# Main.net
KiCad netlist of a schematic drawn in Altium Designer
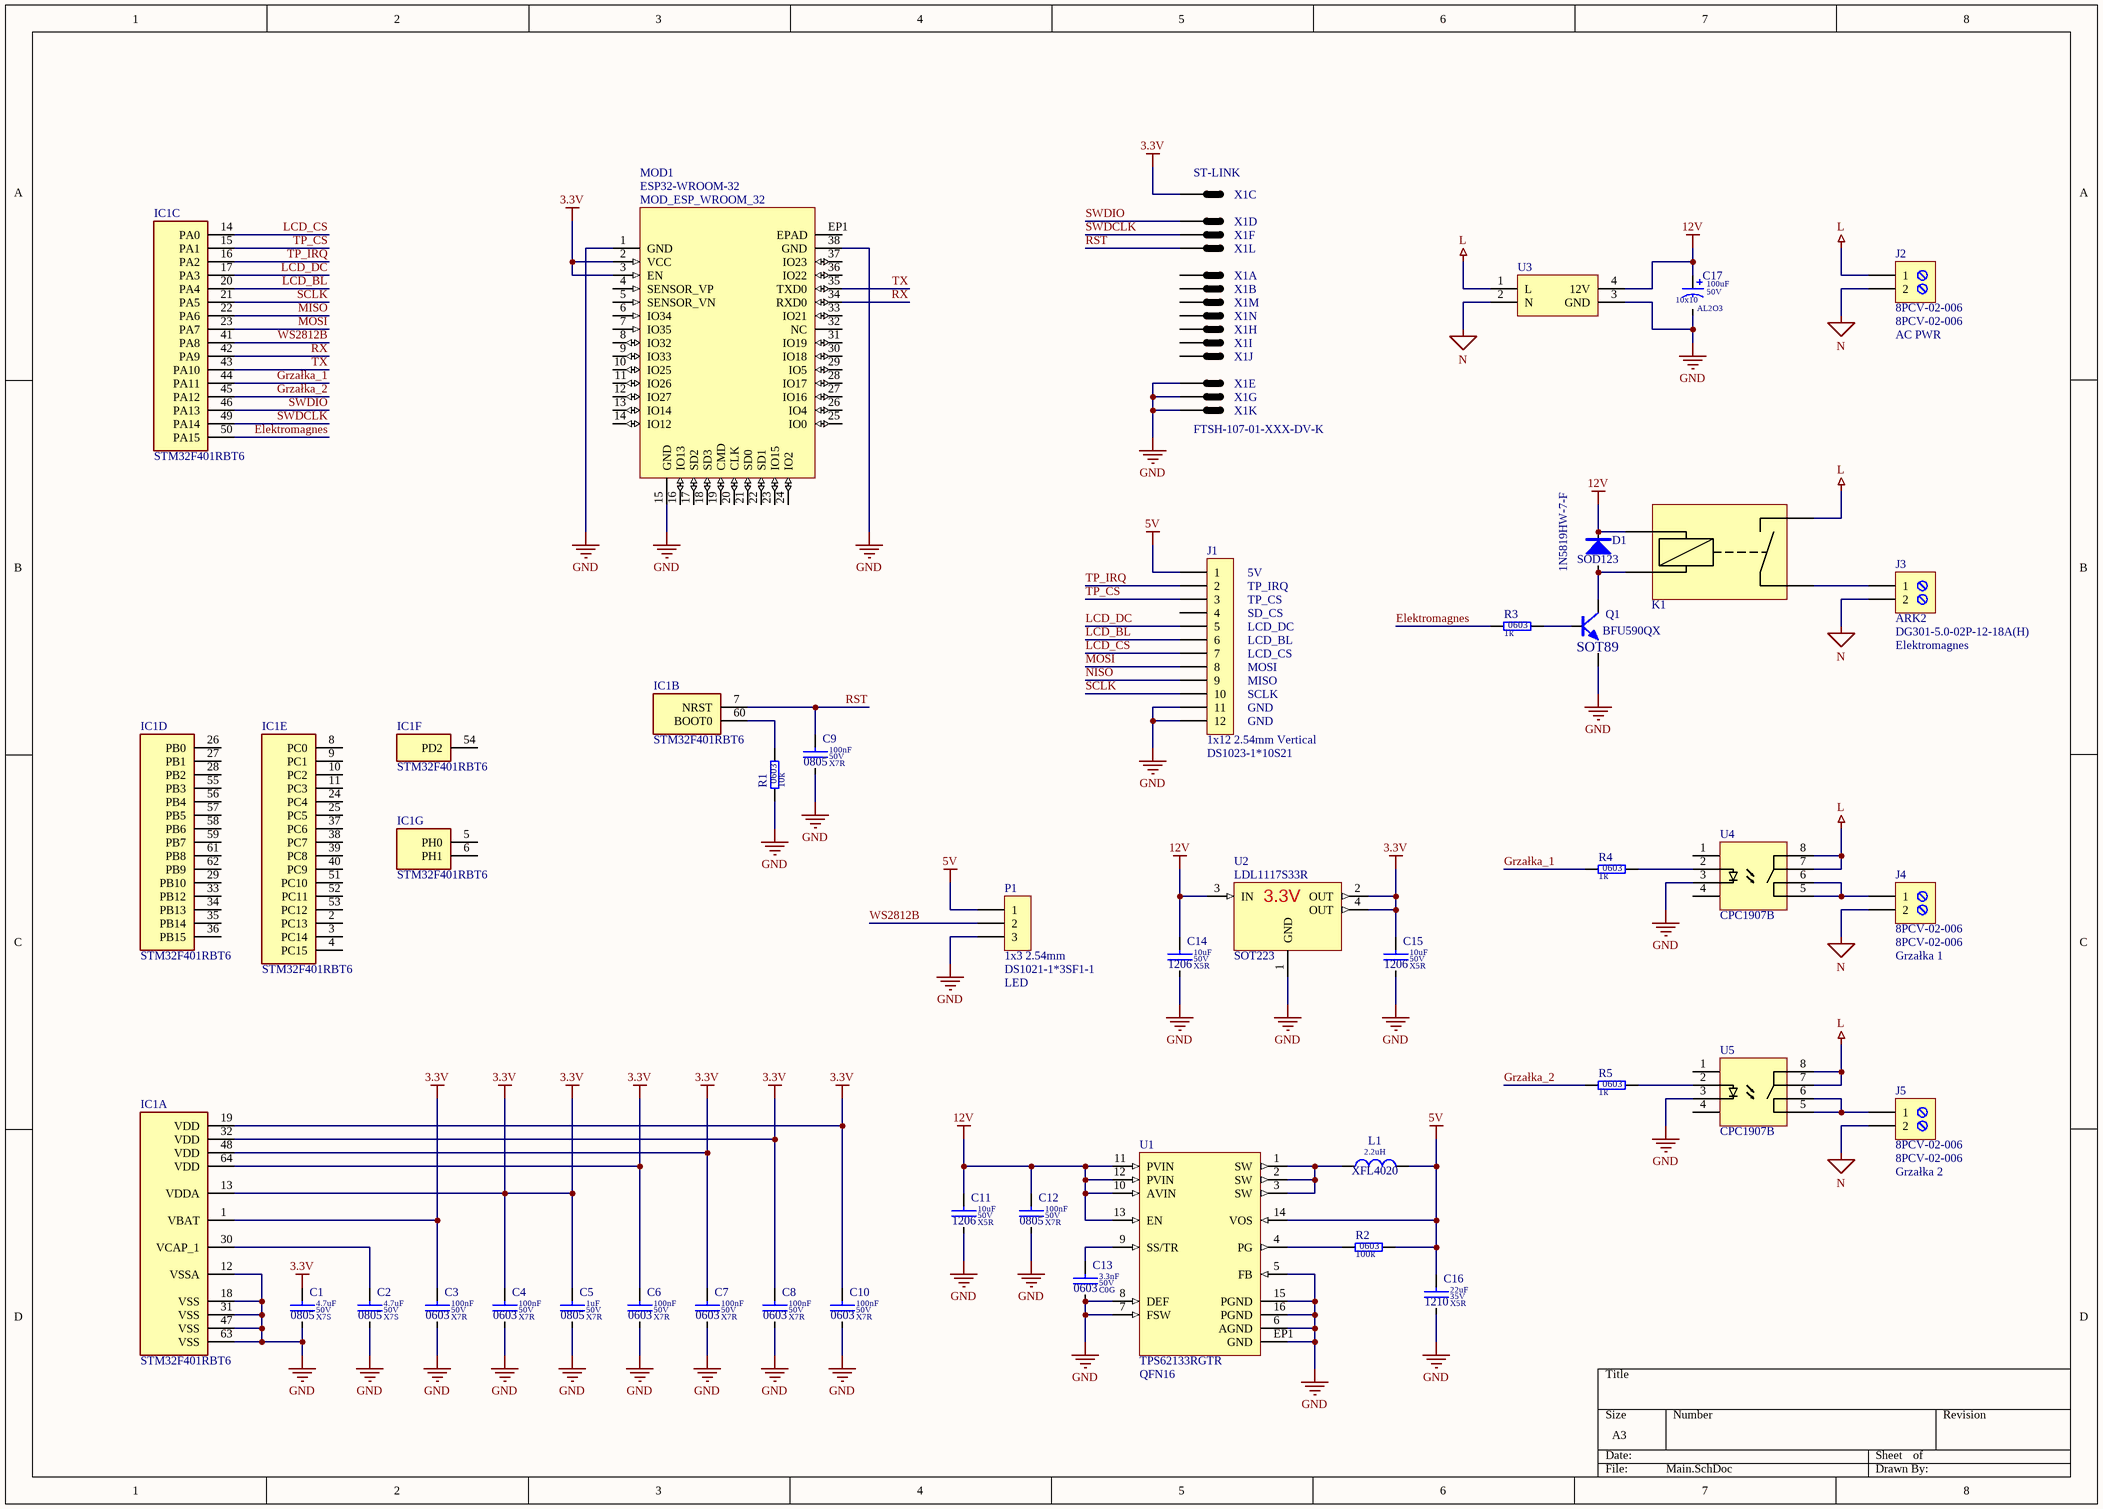
[diagram p0: Main.SchDoc]

(export (version "E")
  (design (tool "Eeschema 10.0.6"))
  (components
    (comp (ref "C1")
      (value "4.7uF")
      (footprint "C_0805_2012")
      (description "Capacitor")
      (fields
        (field (name "DIELECTRIC") "X7S")
        (field (name "VOLTAGE") "50V")
        (field (name "SCH_FOOTPRINT") "0805")
        (field (name "PART NUMBER") "C_4.7uF_50V_X7S_0805_10")
        (field (name "MANUFACTURER") "Murata")
      )
      (libsource (lib "Library") (part "C"))
    )
    (comp (ref "C2")
      (value "4.7uF")
      (footprint "C_0805_2012")
      (description "Capacitor")
      (fields
        (field (name "DIELECTRIC") "X7S")
        (field (name "VOLTAGE") "50V")
        (field (name "SCH_FOOTPRINT") "0805")
        (field (name "PART NUMBER") "C_4.7uF_50V_X7S_0805_10")
        (field (name "MANUFACTURER") "Murata")
      )
      (libsource (lib "Library") (part "C"))
    )
    (comp (ref "C3")
      (value "100nF")
      (footprint "C_0603_1608")
      (description "Capacitor")
      (fields
        (field (name "DIELECTRIC") "X7R")
        (field (name "VOLTAGE") "50V")
        (field (name "SCH_FOOTPRINT") "0603")
        (field (name "PART NUMBER") "C_100nF_50V_X7R_0603_5")
        (field (name "MANUFACTURER") "Samsung")
      )
      (libsource (lib "Library") (part "C"))
    )
    (comp (ref "C4")
      (value "100nF")
      (footprint "C_0603_1608")
      (description "Capacitor")
      (fields
        (field (name "DIELECTRIC") "X7R")
        (field (name "VOLTAGE") "50V")
        (field (name "SCH_FOOTPRINT") "0603")
        (field (name "PART NUMBER") "C_100nF_50V_X7R_0603_5")
        (field (name "MANUFACTURER") "Samsung")
      )
      (libsource (lib "Library") (part "C"))
    )
    (comp (ref "C5")
      (value "1uF")
      (footprint "C_0805_2012")
      (description "Capacitor")
      (fields
        (field (name "DIELECTRIC") "X7R")
        (field (name "VOLTAGE") "50V")
        (field (name "SCH_FOOTPRINT") "0805")
        (field (name "PART NUMBER") "C_1uF_50V_X7R_0805_10")
        (field (name "MANUFACTURER") "AVX")
      )
      (libsource (lib "Library") (part "C"))
    )
    (comp (ref "C6")
      (value "100nF")
      (footprint "C_0603_1608")
      (description "Capacitor")
      (fields
        (field (name "DIELECTRIC") "X7R")
        (field (name "VOLTAGE") "50V")
        (field (name "SCH_FOOTPRINT") "0603")
        (field (name "PART NUMBER") "C_100nF_50V_X7R_0603_5")
        (field (name "MANUFACTURER") "Samsung")
      )
      (libsource (lib "Library") (part "C"))
    )
    (comp (ref "C7")
      (value "100nF")
      (footprint "C_0603_1608")
      (description "Capacitor")
      (fields
        (field (name "DIELECTRIC") "X7R")
        (field (name "VOLTAGE") "50V")
        (field (name "SCH_FOOTPRINT") "0603")
        (field (name "PART NUMBER") "C_100nF_50V_X7R_0603_5")
        (field (name "MANUFACTURER") "Samsung")
      )
      (libsource (lib "Library") (part "C"))
    )
    (comp (ref "C8")
      (value "100nF")
      (footprint "C_0603_1608")
      (description "Capacitor")
      (fields
        (field (name "DIELECTRIC") "X7R")
        (field (name "VOLTAGE") "50V")
        (field (name "SCH_FOOTPRINT") "0603")
        (field (name "PART NUMBER") "C_100nF_50V_X7R_0603_5")
        (field (name "MANUFACTURER") "Samsung")
      )
      (libsource (lib "Library") (part "C"))
    )
    (comp (ref "C9")
      (value "100nF")
      (footprint "C_0805_2012")
      (description "Capacitor")
      (fields
        (field (name "DIELECTRIC") "X7R")
        (field (name "VOLTAGE") "50V")
        (field (name "SCH_FOOTPRINT") "0805")
        (field (name "PART NUMBER") "C_100nF_50V_X7R_0805_10")
        (field (name "MANUFACTURER") "AVX")
      )
      (libsource (lib "Library") (part "C"))
    )
    (comp (ref "C10")
      (value "100nF")
      (footprint "C_0603_1608")
      (description "Capacitor")
      (fields
        (field (name "DIELECTRIC") "X7R")
        (field (name "VOLTAGE") "50V")
        (field (name "SCH_FOOTPRINT") "0603")
        (field (name "PART NUMBER") "C_100nF_50V_X7R_0603_5")
        (field (name "MANUFACTURER") "Samsung")
      )
      (libsource (lib "Library") (part "C"))
    )
    (comp (ref "C11")
      (value "10uF")
      (footprint "C_1206_3216")
      (description "Capacitor")
      (fields
        (field (name "DIELECTRIC") "X5R")
        (field (name "VOLTAGE") "50V")
        (field (name "SCH_FOOTPRINT") "1206")
        (field (name "PART NUMBER") "C_10uF_50V_X5R_1206_10")
        (field (name "MANUFACTURER") "Murata")
      )
      (libsource (lib "Library") (part "C"))
    )
    (comp (ref "C12")
      (value "100nF")
      (footprint "C_0805_2012")
      (description "Capacitor")
      (fields
        (field (name "DIELECTRIC") "X7R")
        (field (name "VOLTAGE") "50V")
        (field (name "SCH_FOOTPRINT") "0805")
        (field (name "PART NUMBER") "C_100nF_50V_X7R_0805_10")
        (field (name "MANUFACTURER") "AVX")
      )
      (libsource (lib "Library") (part "C"))
    )
    (comp (ref "C13")
      (value "3.3nF")
      (footprint "C_0603_1608")
      (description "Capacitor")
      (fields
        (field (name "DIELECTRIC") "C0G")
        (field (name "VOLTAGE") "50V")
        (field (name "SCH_FOOTPRINT") "0603")
        (field (name "PART NUMBER") "C_3.3nF_50V_C0G_0603_5")
        (field (name "MANUFACTURER") "Murata")
      )
      (libsource (lib "Library") (part "C"))
    )
    (comp (ref "C14")
      (value "10uF")
      (footprint "C_1206_3216")
      (description "Capacitor")
      (fields
        (field (name "DIELECTRIC") "X5R")
        (field (name "VOLTAGE") "50V")
        (field (name "SCH_FOOTPRINT") "1206")
        (field (name "PART NUMBER") "C_10uF_50V_X5R_1206_10")
        (field (name "MANUFACTURER") "Murata")
      )
      (libsource (lib "Library") (part "C"))
    )
    (comp (ref "C15")
      (value "10uF")
      (footprint "C_1206_3216")
      (description "Capacitor")
      (fields
        (field (name "DIELECTRIC") "X5R")
        (field (name "VOLTAGE") "50V")
        (field (name "SCH_FOOTPRINT") "1206")
        (field (name "PART NUMBER") "C_10uF_50V_X5R_1206_10")
        (field (name "MANUFACTURER") "Murata")
      )
      (libsource (lib "Library") (part "C"))
    )
    (comp (ref "C16")
      (value "22uF")
      (footprint "C_1210_3225")
      (description "Capacitor")
      (fields
        (field (name "DIELECTRIC") "X5R")
        (field (name "VOLTAGE") "35V")
        (field (name "SCH_FOOTPRINT") "1210")
        (field (name "PART NUMBER") "C_22uF_35V_X5R_1210_20")
        (field (name "MANUFACTURER") "Taiyo Yuden")
      )
      (libsource (lib "Library") (part "C"))
    )
    (comp (ref "C17")
      (value "100uF")
      (footprint "CE_D_10x10_SMD")
      (description "Polarized Capacitor")
      (fields
        (field (name "DIELECTRIC") "AL2O3")
        (field (name "SCH_FOOTPRINT") "10x10")
        (field (name "VOLTAGE") "50V")
        (field (name "PART NUMBER") "CE_100uF_50V_AL2O3_10x10_20")
        (field (name "MANUFACTURER") "Nichicon")
      )
      (libsource (lib "Library") (part "CE"))
    )
    (comp (ref "D1")
      (value "1N5819HW-7-F")
      (footprint "SOD123")
      (fields
        (field (name "SCH_FOOTPRINT") "SOD123")
        (field (name "PART NUMBER") "D_1N5819HW_1A_40V_SOD123")
        (field (name "VOLTAGE") "40V")
        (field (name "MANUFACTURER") "Diodes Inc")
      )
      (libsource (lib "Library") (part "D"))
    )
    (comp (ref "IC1")
      (value "STM32F401RBT6")
      (footprint "LQFP-64")
      (description "ARM Microcontroller")
      (libsource (lib "Components") (part "STM32F401RBT6"))
    )
    (comp (ref "J1")
      (value "DS1023-1*10S21")
      (footprint "J_HEADER_1x12_2.54_VERTICAL")
      (description "Pin Header")
      (fields
        (field (name "SCH_FOOTPRINT") "1x12 2.54mm Vertical")
        (field (name "PART NUMBER") "J_HEADER_1x12_2.54_VERTICAL")
        (field (name "MANUFACTURER") "Connfly")
      )
      (libsource (lib "Library") (part "J_HEADER_1x12"))
    )
    (comp (ref "J2")
      (value "8PCV-02-006")
      (footprint "J_8PCV-02-006")
      (description "ARK Screw terminal, 2-Pin")
      (fields
        (field (name "SCH_FOOTPRINT") "8PCV-02-006")
        (field (name "PART NUMBER") "J_8PCV-02-006")
        (field (name "MANUFACTURER") "TE Connectivity")
      )
      (libsource (lib "Library") (part "J_ARK2"))
    )
    (comp (ref "J3")
      (value "DG301-5.0-02P-12-18A(H)")
      (footprint "J_ARK2")
      (description "ARK Screw terminal, 2-Pin")
      (fields
        (field (name "SCH_FOOTPRINT") "ARK2")
        (field (name "PART NUMBER") "J_TB-5.0-P-2P")
        (field (name "MANUFACTURER") "DEGSON ELECTRONICS")
      )
      (libsource (lib "Library") (part "J_ARK2"))
    )
    (comp (ref "J4")
      (value "8PCV-02-006")
      (footprint "J_8PCV-02-006")
      (description "ARK Screw terminal, 2-Pin")
      (fields
        (field (name "SCH_FOOTPRINT") "8PCV-02-006")
        (field (name "PART NUMBER") "J_8PCV-02-006")
        (field (name "MANUFACTURER") "TE Connectivity")
      )
      (libsource (lib "Library") (part "J_ARK2"))
    )
    (comp (ref "J5")
      (value "8PCV-02-006")
      (footprint "J_8PCV-02-006")
      (description "ARK Screw terminal, 2-Pin")
      (fields
        (field (name "SCH_FOOTPRINT") "8PCV-02-006")
        (field (name "PART NUMBER") "J_8PCV-02-006")
        (field (name "MANUFACTURER") "TE Connectivity")
      )
      (libsource (lib "Library") (part "J_ARK2"))
    )
    (comp (ref "K1")
      (value "FTR-F3AA012E")
      (footprint "FTR-F3AA012E")
      (libsource (lib "SchLib") (part "FTR-F3AA012E"))
    )
    (comp (ref "L1")
      (value "2.2uH")
      (footprint "XFL4020")
      (description "Induction")
      (fields
        (field (name "SCH_FOOTPRINT") "XFL4020")
        (field (name "PART NUMBER") "L_2.2uH_8A_XFL4020")
        (field (name "MANUFACTURER") "Coilcraft")
      )
      (libsource (lib "Library") (part "L"))
    )
    (comp (ref "MOD1")
      (value "ESP32-WROOM-32")
      (footprint "MOD_ESP_WROOM_32")
      (fields
        (field (name "SCH_FOOTPRINT") "MOD_ESP_WROOM_32")
        (field (name "PART NUMBER") "MOD_ESP32-WROOM-32")
        (field (name "MANUFACTURER") "ESPRESSIF")
        (field (name "Comment") "2.4 GHz Wi-Fi-and-Bluetooth combo chip")
      )
      (libsource (lib "Library") (part "MOD_ESP_WROOM_32"))
    )
    (comp (ref "P1")
      (value "DS1021-1*3SF1-1")
      (footprint "P_HEADER_1x3_2.54")
      (description "Pin Header")
      (fields
        (field (name "SCH_FOOTPRINT") "1x3 2.54mm")
        (field (name "PART NUMBER") "P_HEADER_1x3_2.54")
        (field (name "MANUFACTURER") "Connfly")
      )
      (libsource (lib "Library") (part "P_HEADER_1x3"))
    )
    (comp (ref "Q1")
      (value "BFU590QX")
      (footprint "SOT89_TO-243AA_N")
      (fields
        (field (name "SCH_FOOTPRINT") "SOT89")
        (field (name "PART NUMBER") "QNP_BFU590QX")
        (field (name "VOLTAGE") "12V")
        (field (name "MANUFACTURER") "NXP")
      )
      (libsource (lib "Library") (part "QNP_ECB"))
    )
    (comp (ref "R1")
      (value "10k")
      (footprint "R_0603_1608")
      (fields
        (field (name "SCH_FOOTPRINT") "0603")
        (field (name "PART NUMBER") "R_10k_0603_1")
        (field (name "VOLTAGE") "75V")
        (field (name "POWER") "100mW")
      )
      (libsource (lib "Library") (part "R"))
    )
    (comp (ref "R2")
      (value "100k")
      (footprint "R_0603_1608")
      (fields
        (field (name "SCH_FOOTPRINT") "0603")
        (field (name "PART NUMBER") "R_100k_0603_1")
        (field (name "VOLTAGE") "50V")
        (field (name "POWER") "100mW")
      )
      (libsource (lib "Library") (part "R"))
    )
    (comp (ref "R3")
      (value "1k")
      (footprint "R_0603_1608")
      (fields
        (field (name "SCH_FOOTPRINT") "0603")
        (field (name "PART NUMBER") "R_1k_0603_1")
        (field (name "VOLTAGE") "75V")
        (field (name "POWER") "100mW")
      )
      (libsource (lib "Library") (part "R"))
    )
    (comp (ref "R4")
      (value "1k")
      (footprint "R_0603_1608")
      (fields
        (field (name "SCH_FOOTPRINT") "0603")
        (field (name "PART NUMBER") "R_1k_0603_1")
        (field (name "VOLTAGE") "75V")
        (field (name "POWER") "100mW")
      )
      (libsource (lib "Library") (part "R"))
    )
    (comp (ref "R5")
      (value "1k")
      (footprint "R_0603_1608")
      (fields
        (field (name "SCH_FOOTPRINT") "0603")
        (field (name "PART NUMBER") "R_1k_0603_1")
        (field (name "VOLTAGE") "75V")
        (field (name "POWER") "100mW")
      )
      (libsource (lib "Library") (part "R"))
    )
    (comp (ref "U1")
      (value "TPS62133RGTR")
      (footprint "QFN16_3x3")
      (description "3-17V 3A Step-Down Converter with DCS-Control in 3x3 QFN")
      (fields
        (field (name "SCH_FOOTPRINT") "QFN16")
        (field (name "PART NUMBER") "VS_TPS62133RGTR")
        (field (name "MANUFACTURER") "Texas Instruments")
      )
      (libsource (lib "Library") (part "VS_TPS6213x"))
    )
    (comp (ref "U2")
      (value "LDL1117S33R")
      (footprint "SOT223_SC73")
      (description "typical configuration")
      (fields
        (field (name "SCH_FOOTPRINT") "SOT223")
        (field (name "PART NUMBER") "VL_LDL1117S33R")
        (field (name "VOLTAGE") "3.3V")
      )
      (libsource (lib "Library") (part "VL_4pin_3_1_2,4"))
    )
    (comp (ref "U3")
      (value "IRM-30-12")
      (footprint "IRM-30-12")
      (libsource (lib "SchLib") (part "IRM-30-12"))
    )
    (comp (ref "U4") (value "CPC1907B") (footprint "CPC1907B") (libsource (lib "SchLib") (part "CPC1907B")))
    (comp (ref "U5") (value "CPC1907B") (footprint "CPC1907B") (libsource (lib "SchLib") (part "CPC1907B")))
    (comp (ref "X1")
      (value "FTSH-107-01-XXX-DV-K")
      (footprint "FTSH-107-01-XXX-DV-K")
      (description "IDC 14pin male connector")
      (libsource (lib "Connectors") (part "FTSH-107-01-XXX-DV-K"))
    )
  )
  (nets
    (net (code "1") (name "/Elektromagnes") (class "Default")
      (node (ref "IC1") (pin "50") (pinfunction "PA15_50") (pintype "passive"))
      (node (ref "R3") (pin "1") (pinfunction "1_1") (pintype "passive"))
    )
    (net (code "2") (name "/Grzałka_1") (class "Default")
      (node (ref "IC1") (pin "44") (pinfunction "PA11_44") (pintype "passive"))
      (node (ref "R4") (pin "1") (pinfunction "1_1") (pintype "passive"))
    )
    (net (code "3") (name "/Grzałka_2") (class "Default")
      (node (ref "IC1") (pin "45") (pinfunction "PA12_45") (pintype "passive"))
      (node (ref "R5") (pin "1") (pinfunction "1_1") (pintype "passive"))
    )
    (net (code "4") (name "/LCD_BL") (class "Default")
      (node (ref "IC1") (pin "20") (pinfunction "PA4_20") (pintype "passive"))
      (node (ref "J1") (pin "6") (pinfunction "6_6") (pintype "passive"))
    )
    (net (code "5") (name "/LCD_CS") (class "Default")
      (node (ref "IC1") (pin "14") (pinfunction "PA0_14") (pintype "passive"))
      (node (ref "J1") (pin "7") (pinfunction "7_7") (pintype "passive"))
    )
    (net (code "6") (name "/LCD_DC") (class "Default")
      (node (ref "IC1") (pin "17") (pinfunction "PA3_17") (pintype "passive"))
      (node (ref "J1") (pin "5") (pinfunction "5_5") (pintype "passive"))
    )
    (net (code "7") (name "/MISO") (class "Default")
      (node (ref "IC1") (pin "22") (pinfunction "PA6_22") (pintype "passive"))
    )
    (net (code "8") (name "/MOSI") (class "Default")
      (node (ref "IC1") (pin "23") (pinfunction "PA7_23") (pintype "passive"))
      (node (ref "J1") (pin "8") (pinfunction "8_8") (pintype "passive"))
    )
    (net (code "9") (name "/NISO") (class "Default")
      (node (ref "J1") (pin "9") (pinfunction "9_9") (pintype "passive"))
    )
    (net (code "10") (name "/RST") (class "Default")
      (node (ref "C9") (pin "1") (pinfunction "1_1") (pintype "passive"))
      (node (ref "IC1") (pin "7") (pinfunction "NRST_7") (pintype "passive"))
      (node (ref "X1") (pin "12") (pinfunction "12_12") (pintype "passive"))
    )
    (net (code "11") (name "/RX") (class "Default")
      (node (ref "IC1") (pin "42") (pinfunction "PA9_42") (pintype "passive"))
      (node (ref "MOD1") (pin "34") (pinfunction "RXD0_34") (pintype "bidirectional"))
    )
    (net (code "12") (name "/SCLK") (class "Default")
      (node (ref "IC1") (pin "21") (pinfunction "PA5_21") (pintype "passive"))
      (node (ref "J1") (pin "10") (pinfunction "10_10") (pintype "passive"))
    )
    (net (code "13") (name "/SWDCLK") (class "Default")
      (node (ref "IC1") (pin "49") (pinfunction "PA14_49") (pintype "passive"))
      (node (ref "X1") (pin "6") (pinfunction "6_6") (pintype "passive"))
    )
    (net (code "14") (name "/SWDIO") (class "Default")
      (node (ref "IC1") (pin "46") (pinfunction "PA13_46") (pintype "passive"))
      (node (ref "X1") (pin "4") (pinfunction "4_4") (pintype "passive"))
    )
    (net (code "15") (name "/TP_CS") (class "Default")
      (node (ref "IC1") (pin "15") (pinfunction "PA1_15") (pintype "passive"))
      (node (ref "J1") (pin "3") (pinfunction "3_3") (pintype "passive"))
    )
    (net (code "16") (name "/TP_IRQ") (class "Default")
      (node (ref "IC1") (pin "16") (pinfunction "PA2_16") (pintype "passive"))
      (node (ref "J1") (pin "2") (pinfunction "2_2") (pintype "passive"))
    )
    (net (code "17") (name "/TX") (class "Default")
      (node (ref "IC1") (pin "43") (pinfunction "PA10_43") (pintype "passive"))
      (node (ref "MOD1") (pin "35") (pinfunction "TXD0_35") (pintype "bidirectional"))
    )
    (net (code "18") (name "/WS2812B") (class "Default")
      (node (ref "IC1") (pin "41") (pinfunction "PA8_41") (pintype "passive"))
      (node (ref "P1") (pin "2") (pinfunction "2_2") (pintype "passive"))
    )
    (net (code "19") (name "3.3V") (class "Default")
      (node (ref "C1") (pin "1") (pinfunction "1_1") (pintype "passive"))
      (node (ref "C10") (pin "1") (pinfunction "1_1") (pintype "passive"))
      (node (ref "C15") (pin "1") (pinfunction "1_1") (pintype "passive"))
      (node (ref "C3") (pin "1") (pinfunction "1_1") (pintype "passive"))
      (node (ref "C4") (pin "1") (pinfunction "1_1") (pintype "passive"))
      (node (ref "C5") (pin "1") (pinfunction "1_1") (pintype "passive"))
      (node (ref "C6") (pin "1") (pinfunction "1_1") (pintype "passive"))
      (node (ref "C7") (pin "1") (pinfunction "1_1") (pintype "passive"))
      (node (ref "C8") (pin "1") (pinfunction "1_1") (pintype "passive"))
      (node (ref "IC1") (pin "1") (pinfunction "VBAT_1") (pintype "passive"))
      (node (ref "IC1") (pin "13") (pinfunction "VDDA_13") (pintype "passive"))
      (node (ref "IC1") (pin "19") (pinfunction "VDD_19") (pintype "passive"))
      (node (ref "IC1") (pin "32") (pinfunction "VDD_32") (pintype "passive"))
      (node (ref "IC1") (pin "48") (pinfunction "VDD_48") (pintype "passive"))
      (node (ref "IC1") (pin "64") (pinfunction "VDD_64") (pintype "passive"))
      (node (ref "MOD1") (pin "2") (pinfunction "VCC_2") (pintype "input"))
      (node (ref "MOD1") (pin "3") (pinfunction "EN_3") (pintype "input"))
      (node (ref "U2") (pin "2") (pinfunction "OUT_2") (pintype "output"))
      (node (ref "U2") (pin "4") (pinfunction "OUT_4") (pintype "output"))
      (node (ref "X1") (pin "3") (pinfunction "3_3") (pintype "passive"))
    )
    (net (code "20") (name "5V") (class "Default")
      (node (ref "C16") (pin "1") (pinfunction "1_1") (pintype "passive"))
      (node (ref "J1") (pin "1") (pinfunction "1_1") (pintype "passive"))
      (node (ref "L1") (pin "2") (pinfunction "2_2") (pintype "passive"))
      (node (ref "P1") (pin "1") (pinfunction "1_1") (pintype "passive"))
      (node (ref "R2") (pin "2") (pinfunction "2_2") (pintype "passive"))
      (node (ref "U1") (pin "14") (pinfunction "VOS_14") (pintype "input"))
    )
    (net (code "21") (name "12V") (class "Default")
      (node (ref "C11") (pin "1") (pinfunction "1_1") (pintype "passive"))
      (node (ref "C12") (pin "1") (pinfunction "1_1") (pintype "passive"))
      (node (ref "C14") (pin "1") (pinfunction "1_1") (pintype "passive"))
      (node (ref "C17") (pin "1") (pinfunction "1_1") (pintype "passive"))
      (node (ref "D1") (pin "1") (pintype "passive"))
      (node (ref "K1") (pin "1") (pinfunction "1_1") (pintype "passive"))
      (node (ref "U1") (pin "10") (pinfunction "AVIN_10") (pintype "input"))
      (node (ref "U1") (pin "11") (pinfunction "PVIN_11") (pintype "input"))
      (node (ref "U1") (pin "12") (pinfunction "PVIN_12") (pintype "input"))
      (node (ref "U1") (pin "13") (pinfunction "EN_13") (pintype "input"))
      (node (ref "U2") (pin "3") (pinfunction "IN_3") (pintype "input"))
      (node (ref "U3") (pin "4") (pinfunction "12V_4") (pintype "passive"))
    )
    (net (code "22") (name "GND") (class "Default")
      (node (ref "C1") (pin "2") (pinfunction "2_2") (pintype "passive"))
      (node (ref "C10") (pin "2") (pinfunction "2_2") (pintype "passive"))
      (node (ref "C11") (pin "2") (pinfunction "2_2") (pintype "passive"))
      (node (ref "C12") (pin "2") (pinfunction "2_2") (pintype "passive"))
      (node (ref "C13") (pin "2") (pinfunction "2_2") (pintype "passive"))
      (node (ref "C14") (pin "2") (pinfunction "2_2") (pintype "passive"))
      (node (ref "C15") (pin "2") (pinfunction "2_2") (pintype "passive"))
      (node (ref "C16") (pin "2") (pinfunction "2_2") (pintype "passive"))
      (node (ref "C17") (pin "2") (pinfunction "2_2") (pintype "passive"))
      (node (ref "C2") (pin "2") (pinfunction "2_2") (pintype "passive"))
      (node (ref "C3") (pin "2") (pinfunction "2_2") (pintype "passive"))
      (node (ref "C4") (pin "2") (pinfunction "2_2") (pintype "passive"))
      (node (ref "C5") (pin "2") (pinfunction "2_2") (pintype "passive"))
      (node (ref "C6") (pin "2") (pinfunction "2_2") (pintype "passive"))
      (node (ref "C7") (pin "2") (pinfunction "2_2") (pintype "passive"))
      (node (ref "C8") (pin "2") (pinfunction "2_2") (pintype "passive"))
      (node (ref "C9") (pin "2") (pinfunction "2_2") (pintype "passive"))
      (node (ref "IC1") (pin "12") (pinfunction "VSSA_12") (pintype "passive"))
      (node (ref "IC1") (pin "18") (pinfunction "VSS_18") (pintype "passive"))
      (node (ref "IC1") (pin "31") (pinfunction "VSS_31") (pintype "passive"))
      (node (ref "IC1") (pin "47") (pinfunction "VSS_47") (pintype "passive"))
      (node (ref "IC1") (pin "63") (pinfunction "VSS_63") (pintype "passive"))
      (node (ref "J1") (pin "11") (pinfunction "11_11") (pintype "passive"))
      (node (ref "J1") (pin "12") (pinfunction "12_12") (pintype "passive"))
      (node (ref "MOD1") (pin "1") (pinfunction "GND_1") (pintype "power_in"))
      (node (ref "MOD1") (pin "15") (pinfunction "GND_15") (pintype "power_in"))
      (node (ref "MOD1") (pin "38") (pinfunction "GND_38") (pintype "power_in"))
      (node (ref "P1") (pin "3") (pinfunction "3_3") (pintype "passive"))
      (node (ref "Q1") (pin "1") (pinfunction "E_1") (pintype "passive"))
      (node (ref "R1") (pin "1") (pinfunction "1_1") (pintype "passive"))
      (node (ref "U1") (pin "15") (pinfunction "PGND_15") (pintype "power_in"))
      (node (ref "U1") (pin "16") (pinfunction "PGND_16") (pintype "power_in"))
      (node (ref "U1") (pin "5") (pinfunction "FB_5") (pintype "input"))
      (node (ref "U1") (pin "6") (pinfunction "AGND_6") (pintype "power_in"))
      (node (ref "U1") (pin "7") (pinfunction "FSW_7") (pintype "input"))
      (node (ref "U1") (pin "8") (pinfunction "DEF_8") (pintype "input"))
      (node (ref "U1") (pin "EP1") (pinfunction "GND_EP1") (pintype "power_in"))
      (node (ref "U2") (pin "1") (pinfunction "GND_1") (pintype "power_in"))
      (node (ref "U3") (pin "3") (pinfunction "GND_3") (pintype "passive"))
      (node (ref "U4") (pin "3") (pinfunction "3_3") (pintype "passive"))
      (node (ref "U5") (pin "3") (pinfunction "3_3") (pintype "passive"))
      (node (ref "X1") (pin "11") (pinfunction "11_11") (pintype "passive"))
      (node (ref "X1") (pin "5") (pinfunction "5_5") (pintype "passive"))
      (node (ref "X1") (pin "7") (pinfunction "7_7") (pintype "passive"))
    )
    (net (code "23") (name "L") (class "Default")
      (node (ref "J2") (pin "1") (pinfunction "1_1") (pintype "passive"))
      (node (ref "K1") (pin "3") (pinfunction "3_3") (pintype "passive"))
      (node (ref "U3") (pin "1") (pinfunction "L_1") (pintype "passive"))
      (node (ref "U4") (pin "7") (pinfunction "7_7") (pintype "passive"))
      (node (ref "U4") (pin "8") (pinfunction "8_8") (pintype "passive"))
      (node (ref "U5") (pin "7") (pinfunction "7_7") (pintype "passive"))
      (node (ref "U5") (pin "8") (pinfunction "8_8") (pintype "passive"))
    )
    (net (code "24") (name "N") (class "Default")
      (node (ref "J2") (pin "2") (pinfunction "2_2") (pintype "passive"))
      (node (ref "J3") (pin "2") (pinfunction "2_2") (pintype "passive"))
      (node (ref "J4") (pin "2") (pinfunction "2_2") (pintype "passive"))
      (node (ref "J5") (pin "2") (pinfunction "2_2") (pintype "passive"))
      (node (ref "U3") (pin "2") (pinfunction "N_2") (pintype "passive"))
    )
    (net (code "25") (name "Net-(IC1A-VCAP_1)") (class "Default")
      (node (ref "C2") (pin "1") (pinfunction "1_1") (pintype "passive"))
      (node (ref "IC1") (pin "30") (pinfunction "VCAP_1_30") (pintype "passive"))
    )
    (net (code "26") (name "Net-(IC1B-BOOT0)") (class "Default")
      (node (ref "IC1") (pin "60") (pinfunction "BOOT0_60") (pintype "passive"))
      (node (ref "R1") (pin "2") (pinfunction "2_2") (pintype "passive"))
    )
    (net (code "27") (name "Net-(J3-Pad1)") (class "Default")
      (node (ref "J3") (pin "1") (pinfunction "1_1") (pintype "passive"))
      (node (ref "K1") (pin "4") (pinfunction "4_4") (pintype "passive"))
    )
    (net (code "28") (name "Net-(J4-Pad1)") (class "Default")
      (node (ref "J4") (pin "1") (pinfunction "1_1") (pintype "passive"))
      (node (ref "U4") (pin "5") (pinfunction "5_5") (pintype "passive"))
      (node (ref "U4") (pin "6") (pinfunction "6_6") (pintype "passive"))
    )
    (net (code "29") (name "Net-(J5-Pad1)") (class "Default")
      (node (ref "J5") (pin "1") (pinfunction "1_1") (pintype "passive"))
      (node (ref "U5") (pin "5") (pinfunction "5_5") (pintype "passive"))
      (node (ref "U5") (pin "6") (pinfunction "6_6") (pintype "passive"))
    )
    (net (code "30") (name "Net-(L1-Pad1)") (class "Default")
      (node (ref "L1") (pin "1") (pinfunction "1_1") (pintype "passive"))
      (node (ref "U1") (pin "1") (pinfunction "SW_1") (pintype "output"))
      (node (ref "U1") (pin "2") (pinfunction "SW_2") (pintype "output"))
      (node (ref "U1") (pin "3") (pinfunction "SW_3") (pintype "output"))
    )
    (net (code "31") (name "Net-(Q1-B)") (class "Default")
      (node (ref "Q1") (pin "3") (pinfunction "B_3") (pintype "passive"))
      (node (ref "R3") (pin "2") (pinfunction "2_2") (pintype "passive"))
    )
    (net (code "32") (name "Net-(Q1-C)") (class "Default")
      (node (ref "D1") (pin "2") (pintype "passive"))
      (node (ref "K1") (pin "2") (pinfunction "2_2") (pintype "passive"))
      (node (ref "Q1") (pin "2") (pinfunction "C_2") (pintype "passive"))
    )
    (net (code "33") (name "Net-(R4-Pad2)") (class "Default")
      (node (ref "R4") (pin "2") (pinfunction "2_2") (pintype "passive"))
      (node (ref "U4") (pin "2") (pinfunction "2_2") (pintype "passive"))
    )
    (net (code "34") (name "Net-(R5-Pad2)") (class "Default")
      (node (ref "R5") (pin "2") (pinfunction "2_2") (pintype "passive"))
      (node (ref "U5") (pin "2") (pinfunction "2_2") (pintype "passive"))
    )
    (net (code "35") (name "Net-(U1-PG)") (class "Default")
      (node (ref "R2") (pin "1") (pinfunction "1_1") (pintype "passive"))
      (node (ref "U1") (pin "4") (pinfunction "PG_4") (pintype "output"))
    )
    (net (code "36") (name "Net-(U1-SS{slash}TR)") (class "Default")
      (node (ref "C13") (pin "1") (pinfunction "1_1") (pintype "passive"))
      (node (ref "U1") (pin "9") (pinfunction "SS/TR_9") (pintype "input"))
    )
    (net (code "37") (name "unconnected-(IC1D-PB0-Pad26)") (class "Default")
      (node (ref "IC1") (pin "26") (pinfunction "PB0_26") (pintype "passive"))
    )
    (net (code "38") (name "unconnected-(IC1D-PB1-Pad27)") (class "Default")
      (node (ref "IC1") (pin "27") (pinfunction "PB1_27") (pintype "passive"))
    )
    (net (code "39") (name "unconnected-(IC1D-PB2-Pad28)") (class "Default")
      (node (ref "IC1") (pin "28") (pinfunction "PB2_28") (pintype "passive"))
    )
    (net (code "40") (name "unconnected-(IC1D-PB3-Pad55)") (class "Default")
      (node (ref "IC1") (pin "55") (pinfunction "PB3_55") (pintype "passive"))
    )
    (net (code "41") (name "unconnected-(IC1D-PB4-Pad56)") (class "Default")
      (node (ref "IC1") (pin "56") (pinfunction "PB4_56") (pintype "passive"))
    )
    (net (code "42") (name "unconnected-(IC1D-PB5-Pad57)") (class "Default")
      (node (ref "IC1") (pin "57") (pinfunction "PB5_57") (pintype "passive"))
    )
    (net (code "43") (name "unconnected-(IC1D-PB6-Pad58)") (class "Default")
      (node (ref "IC1") (pin "58") (pinfunction "PB6_58") (pintype "passive"))
    )
    (net (code "44") (name "unconnected-(IC1D-PB7-Pad59)") (class "Default")
      (node (ref "IC1") (pin "59") (pinfunction "PB7_59") (pintype "passive"))
    )
    (net (code "45") (name "unconnected-(IC1D-PB8-Pad61)") (class "Default")
      (node (ref "IC1") (pin "61") (pinfunction "PB8_61") (pintype "passive"))
    )
    (net (code "46") (name "unconnected-(IC1D-PB9-Pad62)") (class "Default")
      (node (ref "IC1") (pin "62") (pinfunction "PB9_62") (pintype "passive"))
    )
    (net (code "47") (name "unconnected-(IC1D-PB10-Pad29)") (class "Default")
      (node (ref "IC1") (pin "29") (pinfunction "PB10_29") (pintype "passive"))
    )
    (net (code "48") (name "unconnected-(IC1D-PB12-Pad33)") (class "Default")
      (node (ref "IC1") (pin "33") (pinfunction "PB12_33") (pintype "passive"))
    )
    (net (code "49") (name "unconnected-(IC1D-PB13-Pad34)") (class "Default")
      (node (ref "IC1") (pin "34") (pinfunction "PB13_34") (pintype "passive"))
    )
    (net (code "50") (name "unconnected-(IC1D-PB14-Pad35)") (class "Default")
      (node (ref "IC1") (pin "35") (pinfunction "PB14_35") (pintype "passive"))
    )
    (net (code "51") (name "unconnected-(IC1D-PB15-Pad36)") (class "Default")
      (node (ref "IC1") (pin "36") (pinfunction "PB15_36") (pintype "passive"))
    )
    (net (code "52") (name "unconnected-(IC1E-PC0-Pad8)") (class "Default")
      (node (ref "IC1") (pin "8") (pinfunction "PC0_8") (pintype "passive"))
    )
    (net (code "53") (name "unconnected-(IC1E-PC1-Pad9)") (class "Default")
      (node (ref "IC1") (pin "9") (pinfunction "PC1_9") (pintype "passive"))
    )
    (net (code "54") (name "unconnected-(IC1E-PC2-Pad10)") (class "Default")
      (node (ref "IC1") (pin "10") (pinfunction "PC2_10") (pintype "passive"))
    )
    (net (code "55") (name "unconnected-(IC1E-PC3-Pad11)") (class "Default")
      (node (ref "IC1") (pin "11") (pinfunction "PC3_11") (pintype "passive"))
    )
    (net (code "56") (name "unconnected-(IC1E-PC4-Pad24)") (class "Default")
      (node (ref "IC1") (pin "24") (pinfunction "PC4_24") (pintype "passive"))
    )
    (net (code "57") (name "unconnected-(IC1E-PC5-Pad25)") (class "Default")
      (node (ref "IC1") (pin "25") (pinfunction "PC5_25") (pintype "passive"))
    )
    (net (code "58") (name "unconnected-(IC1E-PC6-Pad37)") (class "Default")
      (node (ref "IC1") (pin "37") (pinfunction "PC6_37") (pintype "passive"))
    )
    (net (code "59") (name "unconnected-(IC1E-PC7-Pad38)") (class "Default")
      (node (ref "IC1") (pin "38") (pinfunction "PC7_38") (pintype "passive"))
    )
    (net (code "60") (name "unconnected-(IC1E-PC8-Pad39)") (class "Default")
      (node (ref "IC1") (pin "39") (pinfunction "PC8_39") (pintype "passive"))
    )
    (net (code "61") (name "unconnected-(IC1E-PC9-Pad40)") (class "Default")
      (node (ref "IC1") (pin "40") (pinfunction "PC9_40") (pintype "passive"))
    )
    (net (code "62") (name "unconnected-(IC1E-PC10-Pad51)") (class "Default")
      (node (ref "IC1") (pin "51") (pinfunction "PC10_51") (pintype "passive"))
    )
    (net (code "63") (name "unconnected-(IC1E-PC11-Pad52)") (class "Default")
      (node (ref "IC1") (pin "52") (pinfunction "PC11_52") (pintype "passive"))
    )
    (net (code "64") (name "unconnected-(IC1E-PC12-Pad53)") (class "Default")
      (node (ref "IC1") (pin "53") (pinfunction "PC12_53") (pintype "passive"))
    )
    (net (code "65") (name "unconnected-(IC1E-PC13-Pad2)") (class "Default")
      (node (ref "IC1") (pin "2") (pinfunction "PC13_2") (pintype "passive"))
    )
    (net (code "66") (name "unconnected-(IC1E-PC14-Pad3)") (class "Default")
      (node (ref "IC1") (pin "3") (pinfunction "PC14_3") (pintype "passive"))
    )
    (net (code "67") (name "unconnected-(IC1E-PC15-Pad4)") (class "Default")
      (node (ref "IC1") (pin "4") (pinfunction "PC15_4") (pintype "passive"))
    )
    (net (code "68") (name "unconnected-(IC1F-PD2-Pad54)") (class "Default")
      (node (ref "IC1") (pin "54") (pinfunction "PD2_54") (pintype "passive"))
    )
    (net (code "69") (name "unconnected-(IC1G-PH0-Pad5)") (class "Default")
      (node (ref "IC1") (pin "5") (pinfunction "PH0_5") (pintype "passive"))
    )
    (net (code "70") (name "unconnected-(IC1G-PH1-Pad6)") (class "Default")
      (node (ref "IC1") (pin "6") (pinfunction "PH1_6") (pintype "passive"))
    )
    (net (code "71") (name "unconnected-(J1-Pad4)") (class "Default")
      (node (ref "J1") (pin "4") (pinfunction "4_4") (pintype "passive"))
    )
    (net (code "72") (name "unconnected-(MOD1-CLK-Pad20)") (class "Default")
      (node (ref "MOD1") (pin "20") (pinfunction "CLK_20") (pintype "bidirectional"))
    )
    (net (code "73") (name "unconnected-(MOD1-CMD-Pad19)") (class "Default")
      (node (ref "MOD1") (pin "19") (pinfunction "CMD_19") (pintype "bidirectional"))
    )
    (net (code "74") (name "unconnected-(MOD1-EPAD-PadEP1)") (class "Default")
      (node (ref "MOD1") (pin "EP1") (pinfunction "EPAD_EP1") (pintype "power_in"))
    )
    (net (code "75") (name "unconnected-(MOD1-IO0-Pad25)") (class "Default")
      (node (ref "MOD1") (pin "25") (pinfunction "IO0_25") (pintype "bidirectional"))
    )
    (net (code "76") (name "unconnected-(MOD1-IO2-Pad24)") (class "Default")
      (node (ref "MOD1") (pin "24") (pinfunction "IO2_24") (pintype "bidirectional"))
    )
    (net (code "77") (name "unconnected-(MOD1-IO4-Pad26)") (class "Default")
      (node (ref "MOD1") (pin "26") (pinfunction "IO4_26") (pintype "bidirectional"))
    )
    (net (code "78") (name "unconnected-(MOD1-IO5-Pad29)") (class "Default")
      (node (ref "MOD1") (pin "29") (pinfunction "IO5_29") (pintype "bidirectional"))
    )
    (net (code "79") (name "unconnected-(MOD1-IO12-Pad14)") (class "Default")
      (node (ref "MOD1") (pin "14") (pinfunction "IO12_14") (pintype "bidirectional"))
    )
    (net (code "80") (name "unconnected-(MOD1-IO13-Pad16)") (class "Default")
      (node (ref "MOD1") (pin "16") (pinfunction "IO13_16") (pintype "bidirectional"))
    )
    (net (code "81") (name "unconnected-(MOD1-IO14-Pad13)") (class "Default")
      (node (ref "MOD1") (pin "13") (pinfunction "IO14_13") (pintype "bidirectional"))
    )
    (net (code "82") (name "unconnected-(MOD1-IO15-Pad23)") (class "Default")
      (node (ref "MOD1") (pin "23") (pinfunction "IO15_23") (pintype "bidirectional"))
    )
    (net (code "83") (name "unconnected-(MOD1-IO16-Pad27)") (class "Default")
      (node (ref "MOD1") (pin "27") (pinfunction "IO16_27") (pintype "bidirectional"))
    )
    (net (code "84") (name "unconnected-(MOD1-IO17-Pad28)") (class "Default")
      (node (ref "MOD1") (pin "28") (pinfunction "IO17_28") (pintype "bidirectional"))
    )
    (net (code "85") (name "unconnected-(MOD1-IO18-Pad30)") (class "Default")
      (node (ref "MOD1") (pin "30") (pinfunction "IO18_30") (pintype "bidirectional"))
    )
    (net (code "86") (name "unconnected-(MOD1-IO19-Pad31)") (class "Default")
      (node (ref "MOD1") (pin "31") (pinfunction "IO19_31") (pintype "bidirectional"))
    )
    (net (code "87") (name "unconnected-(MOD1-IO21-Pad33)") (class "Default")
      (node (ref "MOD1") (pin "33") (pinfunction "IO21_33") (pintype "bidirectional"))
    )
    (net (code "88") (name "unconnected-(MOD1-IO22-Pad36)") (class "Default")
      (node (ref "MOD1") (pin "36") (pinfunction "IO22_36") (pintype "bidirectional"))
    )
    (net (code "89") (name "unconnected-(MOD1-IO23-Pad37)") (class "Default")
      (node (ref "MOD1") (pin "37") (pinfunction "IO23_37") (pintype "bidirectional"))
    )
    (net (code "90") (name "unconnected-(MOD1-IO25-Pad10)") (class "Default")
      (node (ref "MOD1") (pin "10") (pinfunction "IO25_10") (pintype "bidirectional"))
    )
    (net (code "91") (name "unconnected-(MOD1-IO26-Pad11)") (class "Default")
      (node (ref "MOD1") (pin "11") (pinfunction "IO26_11") (pintype "bidirectional"))
    )
    (net (code "92") (name "unconnected-(MOD1-IO27-Pad12)") (class "Default")
      (node (ref "MOD1") (pin "12") (pinfunction "IO27_12") (pintype "bidirectional"))
    )
    (net (code "93") (name "unconnected-(MOD1-IO32-Pad8)") (class "Default")
      (node (ref "MOD1") (pin "8") (pinfunction "IO32_8") (pintype "bidirectional"))
    )
    (net (code "94") (name "unconnected-(MOD1-IO33-Pad9)") (class "Default")
      (node (ref "MOD1") (pin "9") (pinfunction "IO33_9") (pintype "bidirectional"))
    )
    (net (code "95") (name "unconnected-(MOD1-IO34-Pad6)") (class "Default")
      (node (ref "MOD1") (pin "6") (pinfunction "IO34_6") (pintype "input"))
    )
    (net (code "96") (name "unconnected-(MOD1-IO35-Pad7)") (class "Default")
      (node (ref "MOD1") (pin "7") (pinfunction "IO35_7") (pintype "input"))
    )
    (net (code "97") (name "unconnected-(MOD1-NC-Pad32)") (class "Default")
      (node (ref "MOD1") (pin "32") (pinfunction "NC_32") (pintype "passive"))
    )
    (net (code "98") (name "unconnected-(MOD1-SD0-Pad21)") (class "Default")
      (node (ref "MOD1") (pin "21") (pinfunction "SD0_21") (pintype "bidirectional"))
    )
    (net (code "99") (name "unconnected-(MOD1-SD1-Pad22)") (class "Default")
      (node (ref "MOD1") (pin "22") (pinfunction "SD1_22") (pintype "bidirectional"))
    )
    (net (code "100") (name "unconnected-(MOD1-SD2-Pad17)") (class "Default")
      (node (ref "MOD1") (pin "17") (pinfunction "SD2_17") (pintype "bidirectional"))
    )
    (net (code "101") (name "unconnected-(MOD1-SD3-Pad18)") (class "Default")
      (node (ref "MOD1") (pin "18") (pinfunction "SD3_18") (pintype "bidirectional"))
    )
    (net (code "102") (name "unconnected-(MOD1-SENSOR_VN-Pad5)") (class "Default")
      (node (ref "MOD1") (pin "5") (pinfunction "SENSOR_VN_5") (pintype "input"))
    )
    (net (code "103") (name "unconnected-(MOD1-SENSOR_VP-Pad4)") (class "Default")
      (node (ref "MOD1") (pin "4") (pinfunction "SENSOR_VP_4") (pintype "input"))
    )
    (net (code "104") (name "unconnected-(U4-Pad1)") (class "Default")
      (node (ref "U4") (pin "1") (pinfunction "1_1") (pintype "passive"))
    )
    (net (code "105") (name "unconnected-(U4-Pad4)") (class "Default")
      (node (ref "U4") (pin "4") (pinfunction "4_4") (pintype "passive"))
    )
    (net (code "106") (name "unconnected-(U5-Pad1)") (class "Default")
      (node (ref "U5") (pin "1") (pinfunction "1_1") (pintype "passive"))
    )
    (net (code "107") (name "unconnected-(U5-Pad4)") (class "Default")
      (node (ref "U5") (pin "4") (pinfunction "4_4") (pintype "passive"))
    )
    (net (code "108") (name "unconnected-(X1-Pad1)") (class "Default")
      (node (ref "X1") (pin "1") (pinfunction "1_1") (pintype "passive"))
    )
    (net (code "109") (name "unconnected-(X1-Pad2)") (class "Default")
      (node (ref "X1") (pin "2") (pinfunction "2_2") (pintype "passive"))
    )
    (net (code "110") (name "unconnected-(X1-Pad8)") (class "Default")
      (node (ref "X1") (pin "8") (pinfunction "8_8") (pintype "passive"))
    )
    (net (code "111") (name "unconnected-(X1-Pad9)") (class "Default")
      (node (ref "X1") (pin "9") (pinfunction "9_9") (pintype "passive"))
    )
    (net (code "112") (name "unconnected-(X1-Pad10)") (class "Default")
      (node (ref "X1") (pin "10") (pinfunction "10_10") (pintype "passive"))
    )
    (net (code "113") (name "unconnected-(X1-Pad13)") (class "Default")
      (node (ref "X1") (pin "13") (pinfunction "13_13") (pintype "passive"))
    )
    (net (code "114") (name "unconnected-(X1-Pad14)") (class "Default")
      (node (ref "X1") (pin "14") (pinfunction "14_14") (pintype "passive"))
    )
  )
)
